# FubarinoMini_v15.net
KiCad netlist of a schematic drawn in EAGLE
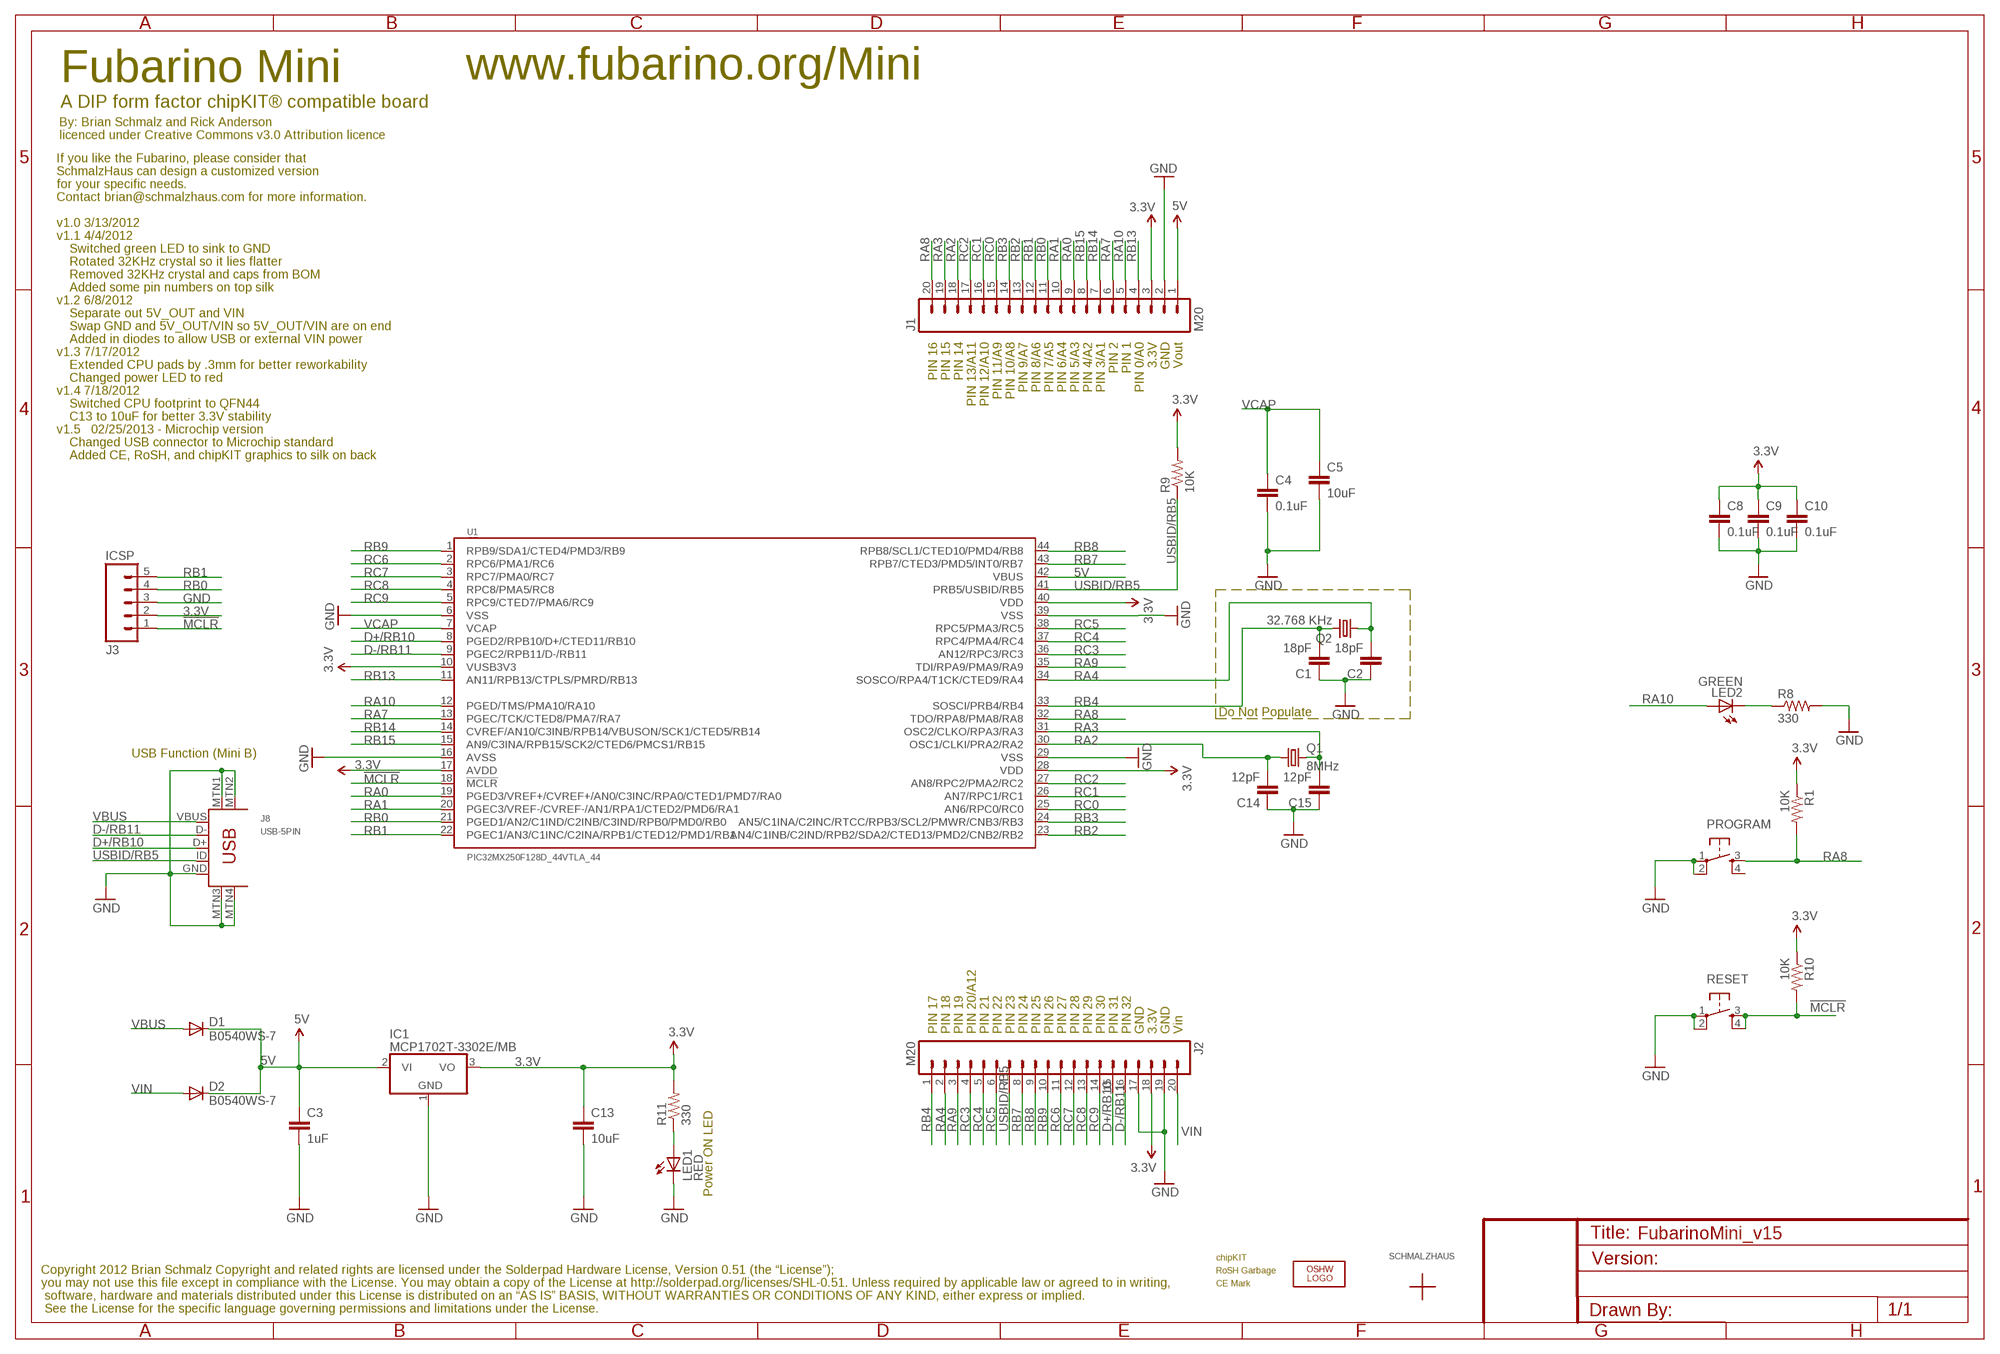
[diagram p0: schematic, sheet 1]

(export (version "E")
  (design (tool "Eeschema 10.0.6"))
  (components
    (comp (ref "C1")
      (value "18pF")
      (footprint "eagle-import:0603-CAP")
      (libsource (lib "eagle-import") (part "SparkFun_CAP0603-CAP"))
    )
    (comp (ref "C2")
      (value "18pF")
      (footprint "eagle-import:0603-CAP")
      (libsource (lib "eagle-import") (part "SparkFun_CAP0603-CAP"))
    )
    (comp (ref "C3")
      (value "1uF")
      (footprint "eagle-import:0603-CAP")
      (libsource (lib "eagle-import") (part "SparkFun_CAP0603-CAP"))
    )
    (comp (ref "C4")
      (value "0.1uF")
      (footprint "eagle-import:0603-CAP")
      (libsource (lib "eagle-import") (part "SparkFun_CAP0603-CAP"))
    )
    (comp (ref "C5")
      (value "10uF")
      (footprint "eagle-import:0805")
      (libsource (lib "eagle-import") (part "CAP0805"))
    )
    (comp (ref "C8")
      (value "0.1uF")
      (footprint "eagle-import:0603-CAP")
      (libsource (lib "eagle-import") (part "SparkFun_CAP0603-CAP"))
    )
    (comp (ref "C9")
      (value "0.1uF")
      (footprint "eagle-import:0603-CAP")
      (libsource (lib "eagle-import") (part "SparkFun_CAP0603-CAP"))
    )
    (comp (ref "C10")
      (value "0.1uF")
      (footprint "eagle-import:0603")
      (libsource (lib "eagle-import") (part "CAP0603"))
    )
    (comp (ref "C13")
      (value "10uF")
      (footprint "eagle-import:0805")
      (libsource (lib "eagle-import") (part "SparkFun02-20-08_CAP0805"))
    )
    (comp (ref "C14")
      (value "12pF")
      (footprint "eagle-import:0603-CAP")
      (libsource (lib "eagle-import") (part "SparkFun_CAP0603-CAP"))
    )
    (comp (ref "C15")
      (value "12pF")
      (footprint "eagle-import:0603-CAP")
      (libsource (lib "eagle-import") (part "SparkFun_CAP0603-CAP"))
    )
    (comp (ref "D1")
      (value "B0540WS-7")
      (footprint "eagle-import:SOD-323")
      (libsource (lib "eagle-import") (part "DIODESOD"))
    )
    (comp (ref "D2")
      (value "B0540WS-7")
      (footprint "eagle-import:SOD-323")
      (libsource (lib "eagle-import") (part "DIODESOD"))
    )
    (comp (ref "IC1")
      (value "MCP1702T-3302E/MB")
      (footprint "eagle-import:SOT89")
      (libsource (lib "eagle-import") (part "MCP1703MB33"))
    )
    (comp (ref "ICSP")
      (value "J3")
      (footprint "eagle-import:1X05_NOSILK")
      (libsource (lib "eagle-import") (part "M05NOSLILK"))
    )
    (comp (ref "J1")
      (value "M20")
      (footprint "eagle-import:1X20_NO_PIN1")
      (libsource (lib "eagle-import") (part "M20"))
    )
    (comp (ref "J2")
      (value "M20")
      (footprint "eagle-import:1X20_NO_PIN1")
      (libsource (lib "eagle-import") (part "M20"))
    )
    (comp (ref "J8")
      (value "USB-5PIN")
      (footprint "eagle-import:USB-MINIB-5PIN-HIROSE-UX60-MB-5ST")
      (libsource (lib "eagle-import") (part "USB-5PIN"))
    )
    (comp (ref "LED1")
      (value "RED")
      (footprint "eagle-import:LED-0603")
      (libsource (lib "eagle-import") (part "LED0603"))
    )
    (comp (ref "LED2")
      (value "GREEN")
      (footprint "eagle-import:LED-0603")
      (libsource (lib "eagle-import") (part "LED0603"))
    )
    (comp (ref "LOGO1")
      (value "OSHW_LOGO_8MILX0070-NT")
      (footprint "eagle-import:OSHW_8X70_NOTEXT")
      (libsource (lib "eagle-import") (part "OSHW_LOGO_8MILX0070-NT"))
    )
    (comp (ref "PROGRAM")
      (value "TAC_SWITCHSND")
      (footprint "eagle-import:TACTILE_SWITCH_SMD")
      (libsource (lib "eagle-import") (part "TAC_SWITCHSND"))
    )
    (comp (ref "Q1")
      (value "8MHz")
      (footprint "eagle-import:NX5032_5MM_3.2MM_CRYSTAL")
      (libsource (lib "eagle-import") (part "CRYSTALNX5032"))
    )
    (comp (ref "Q2")
      (value "32.768 KHz")
      (footprint "eagle-import:TC26H")
      (libsource (lib "eagle-import") (part "CRYSTALTC26H"))
    )
    (comp (ref "R1")
      (value "10K")
      (footprint "eagle-import:0603-RES")
      (libsource (lib "eagle-import") (part "RESISTOR0603-RES"))
    )
    (comp (ref "R8")
      (value "330")
      (footprint "eagle-import:0603-RES")
      (libsource (lib "eagle-import") (part "RESISTOR0603-RES"))
    )
    (comp (ref "R9")
      (value "10K")
      (footprint "eagle-import:0603-RES")
      (libsource (lib "eagle-import") (part "RESISTOR0603-RES"))
    )
    (comp (ref "R10")
      (value "10K")
      (footprint "eagle-import:0603-RES")
      (libsource (lib "eagle-import") (part "RESISTOR0603-RES"))
    )
    (comp (ref "R11")
      (value "330")
      (footprint "eagle-import:0603-RES")
      (libsource (lib "eagle-import") (part "RESISTOR0603-RES"))
    )
    (comp (ref "RESET")
      (value "TAC_SWITCHSND")
      (footprint "eagle-import:TACTILE_SWITCH_SMD")
      (libsource (lib "eagle-import") (part "TAC_SWITCHSND"))
    )
    (comp (ref "U$1")
      (value "SCHMALZHAUSSCHMALZHAUS_SMALL")
      (footprint "eagle-import:SCHMALZHAUS_SMALL")
      (libsource (lib "eagle-import") (part "SCHMALZHAUSSCHMALZHAUS_SMALL"))
    )
    (comp (ref "U$2")
      (value "CE_MARK5MM")
      (footprint "eagle-import:CE_5MM")
      (libsource (lib "eagle-import") (part "CE_MARK5MM"))
    )
    (comp (ref "U$3")
      (value "ROSH_GARBAGE")
      (footprint "eagle-import:ROHS_GARBAGE_5MM")
      (libsource (lib "eagle-import") (part "ROSH_GARBAGE"))
    )
    (comp (ref "U$4")
      (value "CHIPKIT2MM")
      (footprint "eagle-import:CHIPKIT_2MM")
      (libsource (lib "eagle-import") (part "CHIPKIT2MM"))
    )
    (comp (ref "U1")
      (value "PIC32MX250F128D_44VTLA_44")
      (footprint "eagle-import:QFN-44-8X8-NOPAD")
      (libsource (lib "eagle-import") (part "PIC32MX2XX_44QFN44"))
    )
  )
  (nets
    (net (code "1") (name "/D+{slash}RB10") (class "Default")
      (node (ref "J2") (pin "15") (pinfunction "15_15") (pintype "passive"))
      (node (ref "J8") (pin "D+") (pinfunction "D+_D+") (pintype "bidirectional"))
      (node (ref "U1") (pin "8") (pinfunction "PGED2/RPB10/D+/CTED11/RB10_8") (pintype "bidirectional"))
    )
    (net (code "2") (name "/D-{slash}RB11") (class "Default")
      (node (ref "J2") (pin "16") (pinfunction "16_16") (pintype "passive"))
      (node (ref "J8") (pin "D-") (pinfunction "D-_D-") (pintype "bidirectional"))
      (node (ref "U1") (pin "9") (pinfunction "PGEC2/RPB11/D-/RB11_9") (pintype "bidirectional"))
    )
    (net (code "3") (name "/RA0") (class "Default")
      (node (ref "J1") (pin "9") (pinfunction "9_9") (pintype "passive"))
      (node (ref "U1") (pin "19") (pinfunction "PGED3/VREF+/CVREF+/AN0/C3INC/RPA0/CTED1/PMD7/RA0_19") (pintype "bidirectional"))
    )
    (net (code "4") (name "/RA1") (class "Default")
      (node (ref "J1") (pin "10") (pinfunction "10_10") (pintype "passive"))
      (node (ref "U1") (pin "20") (pinfunction "PGEC3/VREF-/CVREF-/AN1/RPA1/CTED2/PMD6/RA1_20") (pintype "bidirectional"))
    )
    (net (code "5") (name "/RA2") (class "Default")
      (node (ref "C14") (pin "2") (pinfunction "2_2") (pintype "passive"))
      (node (ref "J1") (pin "18") (pinfunction "18_18") (pintype "passive"))
      (node (ref "Q1") (pin "1") (pinfunction "1_1") (pintype "passive"))
      (node (ref "U1") (pin "30") (pinfunction "OSC1/CLKI/PRA2/RA2_30") (pintype "bidirectional"))
    )
    (net (code "6") (name "/RA3") (class "Default")
      (node (ref "C15") (pin "2") (pinfunction "2_2") (pintype "passive"))
      (node (ref "J1") (pin "19") (pinfunction "19_19") (pintype "passive"))
      (node (ref "Q1") (pin "2") (pinfunction "2_2") (pintype "passive"))
      (node (ref "U1") (pin "31") (pinfunction "OSC2/CLKO/RPA3/RA3_31") (pintype "bidirectional"))
    )
    (net (code "7") (name "/RA4") (class "Default")
      (node (ref "C2") (pin "2") (pinfunction "2_2") (pintype "passive"))
      (node (ref "J2") (pin "2") (pinfunction "2_2") (pintype "passive"))
      (node (ref "Q2") (pin "1") (pinfunction "1_1") (pintype "passive"))
      (node (ref "U1") (pin "34") (pinfunction "SOSCO/RPA4/T1CK/CTED9/RA4_34") (pintype "bidirectional"))
    )
    (net (code "8") (name "/RA7") (class "Default")
      (node (ref "J1") (pin "6") (pinfunction "6_6") (pintype "passive"))
      (node (ref "U1") (pin "13") (pinfunction "PGEC/TCK/CTED8/PMA7/RA7_13") (pintype "bidirectional"))
    )
    (net (code "9") (name "/RA8") (class "Default")
      (node (ref "J1") (pin "20") (pinfunction "20_20") (pintype "passive"))
      (node (ref "PROGRAM") (pin "3") (pinfunction "3_3") (pintype "passive"))
      (node (ref "R1") (pin "2") (pinfunction "2_2") (pintype "passive"))
      (node (ref "U1") (pin "32") (pinfunction "TDO/RPA8/PMA8/RA8_32") (pintype "bidirectional"))
    )
    (net (code "10") (name "/RA9") (class "Default")
      (node (ref "J2") (pin "3") (pinfunction "3_3") (pintype "passive"))
      (node (ref "U1") (pin "35") (pinfunction "TDI/RPA9/PMA9/RA9_35") (pintype "bidirectional"))
    )
    (net (code "11") (name "/RA10") (class "Default")
      (node (ref "J1") (pin "5") (pinfunction "5_5") (pintype "passive"))
      (node (ref "LED2") (pin "A") (pinfunction "A_A") (pintype "passive"))
      (node (ref "U1") (pin "12") (pinfunction "PGED/TMS/PMA10/RA10_12") (pintype "bidirectional"))
    )
    (net (code "12") (name "/RB0") (class "Default")
      (node (ref "ICSP") (pin "4") (pinfunction "4_4") (pintype "passive"))
      (node (ref "J1") (pin "11") (pinfunction "11_11") (pintype "passive"))
      (node (ref "U1") (pin "21") (pinfunction "PGED1/AN2/C1IND/C2INB/C3IND/RPB0/PMD0/RB0_21") (pintype "bidirectional"))
    )
    (net (code "13") (name "/RB1") (class "Default")
      (node (ref "ICSP") (pin "5") (pinfunction "5_5") (pintype "passive"))
      (node (ref "J1") (pin "12") (pinfunction "12_12") (pintype "passive"))
      (node (ref "U1") (pin "22") (pinfunction "PGEC1/AN3/C1INC/C2INA/RPB1/CTED12/PMD1/RB1_22") (pintype "bidirectional"))
    )
    (net (code "14") (name "/RB2") (class "Default")
      (node (ref "J1") (pin "13") (pinfunction "13_13") (pintype "passive"))
      (node (ref "U1") (pin "23") (pinfunction "AN4/C1INB/C2IND/RPB2/SDA2/CTED13/PMD2/CNB2/RB2_23") (pintype "bidirectional"))
    )
    (net (code "15") (name "/RB3") (class "Default")
      (node (ref "J1") (pin "14") (pinfunction "14_14") (pintype "passive"))
      (node (ref "U1") (pin "24") (pinfunction "AN5/C1INA/C2INC/RTCC/RPB3/SCL2/PMWR/CNB3/RB3_24") (pintype "bidirectional"))
    )
    (net (code "16") (name "/RB4") (class "Default")
      (node (ref "C1") (pin "2") (pinfunction "2_2") (pintype "passive"))
      (node (ref "J2") (pin "1") (pinfunction "1_1") (pintype "passive"))
      (node (ref "Q2") (pin "2") (pinfunction "2_2") (pintype "passive"))
      (node (ref "U1") (pin "33") (pinfunction "SOSCI/PRB4/RB4_33") (pintype "bidirectional"))
    )
    (net (code "17") (name "/RB7") (class "Default")
      (node (ref "J2") (pin "8") (pinfunction "8_8") (pintype "passive"))
      (node (ref "U1") (pin "43") (pinfunction "RPB7/CTED3/PMD5/INT0/RB7_43") (pintype "bidirectional"))
    )
    (net (code "18") (name "/RB8") (class "Default")
      (node (ref "J2") (pin "9") (pinfunction "9_9") (pintype "passive"))
      (node (ref "U1") (pin "44") (pinfunction "RPB8/SCL1/CTED10/PMD4/RB8_44") (pintype "bidirectional"))
    )
    (net (code "19") (name "/RB9") (class "Default")
      (node (ref "J2") (pin "10") (pinfunction "10_10") (pintype "passive"))
      (node (ref "U1") (pin "1") (pinfunction "RPB9/SDA1/CTED4/PMD3/RB9_1") (pintype "bidirectional"))
    )
    (net (code "20") (name "/RB13") (class "Default")
      (node (ref "J1") (pin "4") (pinfunction "4_4") (pintype "passive"))
      (node (ref "U1") (pin "11") (pinfunction "AN11/RPB13/CTPLS/PMRD/RB13_11") (pintype "bidirectional"))
    )
    (net (code "21") (name "/RB14") (class "Default")
      (node (ref "J1") (pin "7") (pinfunction "7_7") (pintype "passive"))
      (node (ref "U1") (pin "14") (pinfunction "CVREF/AN10/C3INB/RPB14/VBUSON/SCK1/CTED5/RB14_14") (pintype "bidirectional"))
    )
    (net (code "22") (name "/RB15") (class "Default")
      (node (ref "J1") (pin "8") (pinfunction "8_8") (pintype "passive"))
      (node (ref "U1") (pin "15") (pinfunction "AN9/C3INA/RPB15/SCK2/CTED6/PMCS1/RB15_15") (pintype "bidirectional"))
    )
    (net (code "23") (name "/RC0") (class "Default")
      (node (ref "J1") (pin "15") (pinfunction "15_15") (pintype "passive"))
      (node (ref "U1") (pin "25") (pinfunction "AN6/RPC0/RC0_25") (pintype "bidirectional"))
    )
    (net (code "24") (name "/RC1") (class "Default")
      (node (ref "J1") (pin "16") (pinfunction "16_16") (pintype "passive"))
      (node (ref "U1") (pin "26") (pinfunction "AN7/RPC1/RC1_26") (pintype "bidirectional"))
    )
    (net (code "25") (name "/RC2") (class "Default")
      (node (ref "J1") (pin "17") (pinfunction "17_17") (pintype "passive"))
      (node (ref "U1") (pin "27") (pinfunction "AN8/RPC2/PMA2/RC2_27") (pintype "bidirectional"))
    )
    (net (code "26") (name "/RC3") (class "Default")
      (node (ref "J2") (pin "4") (pinfunction "4_4") (pintype "passive"))
      (node (ref "U1") (pin "36") (pinfunction "AN12/RPC3/RC3_36") (pintype "bidirectional"))
    )
    (net (code "27") (name "/RC4") (class "Default")
      (node (ref "J2") (pin "5") (pinfunction "5_5") (pintype "passive"))
      (node (ref "U1") (pin "37") (pinfunction "RPC4/PMA4/RC4_37") (pintype "bidirectional"))
    )
    (net (code "28") (name "/RC5") (class "Default")
      (node (ref "J2") (pin "6") (pinfunction "6_6") (pintype "passive"))
      (node (ref "U1") (pin "38") (pinfunction "RPC5/PMA3/RC5_38") (pintype "bidirectional"))
    )
    (net (code "29") (name "/RC6") (class "Default")
      (node (ref "J2") (pin "11") (pinfunction "11_11") (pintype "passive"))
      (node (ref "U1") (pin "2") (pinfunction "RPC6/PMA1/RC6_2") (pintype "bidirectional"))
    )
    (net (code "30") (name "/RC7") (class "Default")
      (node (ref "J2") (pin "12") (pinfunction "12_12") (pintype "passive"))
      (node (ref "U1") (pin "3") (pinfunction "RPC7/PMA0/RC7_3") (pintype "bidirectional"))
    )
    (net (code "31") (name "/RC8") (class "Default")
      (node (ref "J2") (pin "13") (pinfunction "13_13") (pintype "passive"))
      (node (ref "U1") (pin "4") (pinfunction "RPC8/PMA5/RC8_4") (pintype "bidirectional"))
    )
    (net (code "32") (name "/RC9") (class "Default")
      (node (ref "J2") (pin "14") (pinfunction "14_14") (pintype "passive"))
      (node (ref "U1") (pin "5") (pinfunction "RPC9/CTED7/PMA6/RC9_5") (pintype "bidirectional"))
    )
    (net (code "33") (name "/USBID{slash}RB5") (class "Default")
      (node (ref "J2") (pin "7") (pinfunction "7_7") (pintype "passive"))
      (node (ref "J8") (pin "ID") (pinfunction "ID_ID") (pintype "bidirectional"))
      (node (ref "R9") (pin "1") (pinfunction "1_1") (pintype "passive"))
      (node (ref "U1") (pin "41") (pinfunction "PRB5/USBID/RB5_41") (pintype "bidirectional"))
    )
    (net (code "34") (name "/VBUS") (class "Default")
      (node (ref "D1") (pin "2") (pinfunction "A_2") (pintype "passive"))
      (node (ref "J8") (pin "VBUS") (pinfunction "VBUS_VBUS") (pintype "bidirectional"))
    )
    (net (code "35") (name "/VCAP") (class "Default")
      (node (ref "C4") (pin "1") (pinfunction "1_1") (pintype "passive"))
      (node (ref "C5") (pin "1") (pinfunction "1_1") (pintype "passive"))
      (node (ref "U1") (pin "7") (pinfunction "VCAP_7") (pintype "bidirectional"))
    )
    (net (code "36") (name "/VIN") (class "Default")
      (node (ref "D2") (pin "2") (pinfunction "A_2") (pintype "passive"))
      (node (ref "J2") (pin "20") (pinfunction "20_20") (pintype "passive"))
    )
    (net (code "37") (name "/~{MCLR}") (class "Default")
      (node (ref "ICSP") (pin "1") (pinfunction "1_1") (pintype "passive"))
      (node (ref "R10") (pin "2") (pinfunction "2_2") (pintype "passive"))
      (node (ref "RESET") (pin "3") (pinfunction "3_3") (pintype "passive"))
      (node (ref "RESET") (pin "4") (pinfunction "4_4") (pintype "passive"))
      (node (ref "U1") (pin "18") (pinfunction "~{MCLR}_18") (pintype "bidirectional"))
    )
    (net (code "38") (name "3.3V") (class "Default")
      (node (ref "C10") (pin "1") (pinfunction "1_1") (pintype "passive"))
      (node (ref "C13") (pin "1") (pinfunction "1_1") (pintype "passive"))
      (node (ref "C8") (pin "1") (pinfunction "1_1") (pintype "passive"))
      (node (ref "C9") (pin "1") (pinfunction "1_1") (pintype "passive"))
      (node (ref "IC1") (pin "3") (pinfunction "VO_3") (pintype "passive"))
      (node (ref "ICSP") (pin "2") (pinfunction "2_2") (pintype "passive"))
      (node (ref "J1") (pin "3") (pinfunction "3_3") (pintype "passive"))
      (node (ref "J2") (pin "18") (pinfunction "18_18") (pintype "passive"))
      (node (ref "R1") (pin "1") (pinfunction "1_1") (pintype "passive"))
      (node (ref "R10") (pin "1") (pinfunction "1_1") (pintype "passive"))
      (node (ref "R11") (pin "2") (pinfunction "2_2") (pintype "passive"))
      (node (ref "R9") (pin "2") (pinfunction "2_2") (pintype "passive"))
      (node (ref "U1") (pin "10") (pinfunction "VUSB3V3_10") (pintype "bidirectional"))
      (node (ref "U1") (pin "17") (pinfunction "AVDD_17") (pintype "bidirectional"))
      (node (ref "U1") (pin "28") (pinfunction "VDD_28") (pintype "bidirectional"))
      (node (ref "U1") (pin "40") (pinfunction "VDD_40") (pintype "bidirectional"))
    )
    (net (code "39") (name "5V") (class "Default")
      (node (ref "C3") (pin "1") (pinfunction "1_1") (pintype "passive"))
      (node (ref "D1") (pin "1") (pinfunction "C_1") (pintype "passive"))
      (node (ref "D2") (pin "1") (pinfunction "C_1") (pintype "passive"))
      (node (ref "IC1") (pin "2") (pinfunction "VI_2") (pintype "input"))
      (node (ref "IC1") (pin "2@1") (pinfunction "VI1_2@1") (pintype "input"))
      (node (ref "J1") (pin "1") (pinfunction "1_1") (pintype "passive"))
      (node (ref "U1") (pin "42") (pinfunction "VBUS_42") (pintype "bidirectional"))
    )
    (net (code "40") (name "GND") (class "Default")
      (node (ref "C1") (pin "1") (pinfunction "1_1") (pintype "passive"))
      (node (ref "C10") (pin "2") (pinfunction "2_2") (pintype "passive"))
      (node (ref "C13") (pin "2") (pinfunction "2_2") (pintype "passive"))
      (node (ref "C14") (pin "1") (pinfunction "1_1") (pintype "passive"))
      (node (ref "C15") (pin "1") (pinfunction "1_1") (pintype "passive"))
      (node (ref "C2") (pin "1") (pinfunction "1_1") (pintype "passive"))
      (node (ref "C3") (pin "2") (pinfunction "2_2") (pintype "passive"))
      (node (ref "C4") (pin "2") (pinfunction "2_2") (pintype "passive"))
      (node (ref "C5") (pin "2") (pinfunction "2_2") (pintype "passive"))
      (node (ref "C8") (pin "2") (pinfunction "2_2") (pintype "passive"))
      (node (ref "C9") (pin "2") (pinfunction "2_2") (pintype "passive"))
      (node (ref "IC1") (pin "1") (pinfunction "GND_1") (pintype "passive"))
      (node (ref "ICSP") (pin "3") (pinfunction "3_3") (pintype "passive"))
      (node (ref "J1") (pin "2") (pinfunction "2_2") (pintype "passive"))
      (node (ref "J2") (pin "17") (pinfunction "17_17") (pintype "passive"))
      (node (ref "J2") (pin "19") (pinfunction "19_19") (pintype "passive"))
      (node (ref "J8") (pin "GND") (pinfunction "GND_GND") (pintype "bidirectional"))
      (node (ref "J8") (pin "MTN1") (pinfunction "MTN1_MTN1") (pintype "bidirectional"))
      (node (ref "J8") (pin "MTN2") (pinfunction "MTN2_MTN2") (pintype "bidirectional"))
      (node (ref "J8") (pin "MTN3") (pinfunction "MTN3_MTN3") (pintype "bidirectional"))
      (node (ref "J8") (pin "MTN4") (pinfunction "MTN4_MTN4") (pintype "bidirectional"))
      (node (ref "LED1") (pin "C") (pinfunction "C_C") (pintype "passive"))
      (node (ref "PROGRAM") (pin "1") (pinfunction "1_1") (pintype "passive"))
      (node (ref "PROGRAM") (pin "2") (pinfunction "2_2") (pintype "passive"))
      (node (ref "R8") (pin "2") (pinfunction "2_2") (pintype "passive"))
      (node (ref "RESET") (pin "1") (pinfunction "1_1") (pintype "passive"))
      (node (ref "RESET") (pin "2") (pinfunction "2_2") (pintype "passive"))
      (node (ref "U1") (pin "16") (pinfunction "AVSS_16") (pintype "bidirectional"))
      (node (ref "U1") (pin "29") (pinfunction "VSS_29") (pintype "bidirectional"))
      (node (ref "U1") (pin "39") (pinfunction "VSS_39") (pintype "bidirectional"))
      (node (ref "U1") (pin "6") (pinfunction "VSS_6") (pintype "bidirectional"))
    )
    (net (code "41") (name "Net-(LED1-PadA)") (class "Default")
      (node (ref "LED1") (pin "A") (pinfunction "A_A") (pintype "passive"))
      (node (ref "R11") (pin "1") (pinfunction "1_1") (pintype "passive"))
    )
    (net (code "42") (name "Net-(LED2-PadC)") (class "Default")
      (node (ref "LED2") (pin "C") (pinfunction "C_C") (pintype "passive"))
      (node (ref "R8") (pin "1") (pinfunction "1_1") (pintype "passive"))
    )
    (net (code "43") (name "unconnected-(PROGRAM-Pad4)") (class "Default")
      (node (ref "PROGRAM") (pin "4") (pinfunction "4_4") (pintype "passive"))
    )
  )
)
